# PiezoPreamp_VR.net
KiCad netlist of a schematic drawn in EAGLE
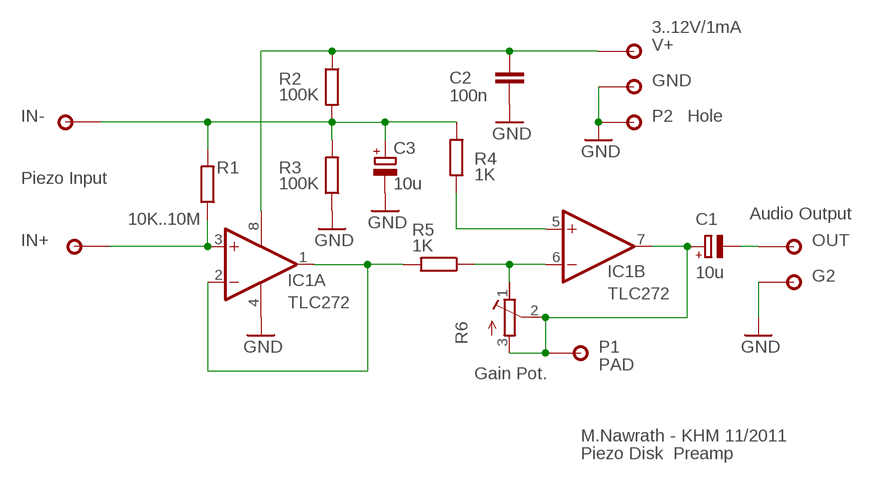
[diagram p0: schematic, sheet 1]

(export (version "E")
  (design (tool "Eeschema 10.0.6"))
  (components
    (comp (ref "C1")
      (value "10u")
      (footprint "eagle-import:E2,5-5")
      (libsource (lib "eagle-import") (part "CPOL-EUE2.5-5"))
    )
    (comp (ref "C2")
      (value "100n")
      (footprint "eagle-import:C025-025X050")
      (libsource (lib "eagle-import") (part "C-EU025-025X050"))
    )
    (comp (ref "C3")
      (value "10u")
      (footprint "eagle-import:E2,5-5")
      (libsource (lib "eagle-import") (part "CPOL-EUE2.5-5"))
    )
    (comp (ref "G2")
      (value "PAD1,46MM")
      (footprint "eagle-import:PAD146")
      (libsource (lib "eagle-import") (part "PAD1,46MM"))
    )
    (comp (ref "GND")
      (value "PAD1,46MM")
      (footprint "eagle-import:PAD146")
      (libsource (lib "eagle-import") (part "PAD1,46MM"))
    )
    (comp (ref "IC1")
      (value "TLC272")
      (footprint "eagle-import:DIL08")
      (libsource (lib "eagle-import") (part "TLC272P"))
    )
    (comp (ref "IN+")
      (value "PAD1,46MM")
      (footprint "eagle-import:PAD146")
      (libsource (lib "eagle-import") (part "PAD1,46MM"))
    )
    (comp (ref "IN-")
      (value "PAD1,46MM")
      (footprint "eagle-import:PAD146")
      (libsource (lib "eagle-import") (part "PAD1,46MM"))
    )
    (comp (ref "OUT")
      (value "PAD1,46MM")
      (footprint "eagle-import:PAD146")
      (libsource (lib "eagle-import") (part "PAD1,46MM"))
    )
    (comp (ref "P1")
      (value "PAD")
      (footprint "eagle-import:PAD127L1")
      (libsource (lib "eagle-import") (part "PADL2"))
    )
    (comp (ref "P2")
      (value "Hole")
      (footprint "eagle-import:PAD146")
      (libsource (lib "eagle-import") (part "PAD1,46MM"))
    )
    (comp (ref "R1")
      (value "10K..10M")
      (footprint "eagle-import:0207_10")
      (libsource (lib "eagle-import") (part "R-EU_0207/10"))
    )
    (comp (ref "R2")
      (value "100K")
      (footprint "eagle-import:0207_10")
      (libsource (lib "eagle-import") (part "R-EU_0207/10"))
    )
    (comp (ref "R3")
      (value "100K")
      (footprint "eagle-import:0207_10")
      (libsource (lib "eagle-import") (part "R-EU_0207/10"))
    )
    (comp (ref "R4")
      (value "1K")
      (footprint "eagle-import:0207_10")
      (libsource (lib "eagle-import") (part "R-EU_0207/10"))
    )
    (comp (ref "R5")
      (value "1K")
      (footprint "eagle-import:0207_10")
      (libsource (lib "eagle-import") (part "R-EU_0207/10"))
    )
    (comp (ref "R6")
      (value "R-TRIMM3006P")
      (footprint "eagle-import:RTRIM3006P")
      (libsource (lib "eagle-import") (part "R-TRIMM3006P"))
    )
    (comp (ref "V+")
      (value "PAD1,46MM")
      (footprint "eagle-import:PAD146")
      (libsource (lib "eagle-import") (part "PAD1,46MM"))
    )
  )
  (nets
    (net (code "1") (name "GND") (class "Default")
      (node (ref "C2") (pin "1") (pinfunction "1_1") (pintype "passive"))
      (node (ref "C3") (pin "-") (pinfunction "-_-") (pintype "passive"))
      (node (ref "G2") (pin "1") (pinfunction "1_1") (pintype "passive"))
      (node (ref "GND") (pin "1") (pinfunction "1_1") (pintype "passive"))
      (node (ref "IC1") (pin "4") (pinfunction "V-_4") (pintype "power_in"))
      (node (ref "P2") (pin "1") (pinfunction "1_1") (pintype "passive"))
      (node (ref "R3") (pin "1") (pinfunction "1_1") (pintype "passive"))
    )
    (net (code "2") (name "Net-(C1-Pad-)") (class "Default")
      (node (ref "C1") (pin "-") (pinfunction "-_-") (pintype "passive"))
      (node (ref "OUT") (pin "1") (pinfunction "1_1") (pintype "passive"))
    )
    (net (code "3") (name "Net-(C3-Pad+)") (class "Default")
      (node (ref "C3") (pin "+") (pinfunction "+_+") (pintype "passive"))
      (node (ref "IN-") (pin "1") (pinfunction "1_1") (pintype "passive"))
      (node (ref "R1") (pin "2") (pinfunction "2_2") (pintype "passive"))
      (node (ref "R2") (pin "2") (pinfunction "2_2") (pintype "passive"))
      (node (ref "R3") (pin "2") (pinfunction "2_2") (pintype "passive"))
      (node (ref "R4") (pin "2") (pinfunction "2_2") (pintype "passive"))
    )
    (net (code "4") (name "Net-(IC1A-+IN)") (class "Default")
      (node (ref "IC1") (pin "3") (pinfunction "+IN_3") (pintype "input"))
      (node (ref "IN+") (pin "1") (pinfunction "1_1") (pintype "passive"))
      (node (ref "R1") (pin "1") (pinfunction "1_1") (pintype "passive"))
    )
    (net (code "5") (name "Net-(IC1A--IN)") (class "Default")
      (node (ref "IC1") (pin "1") (pinfunction "OUT_1") (pintype "output"))
      (node (ref "IC1") (pin "2") (pinfunction "-IN_2") (pintype "input"))
      (node (ref "R5") (pin "2") (pinfunction "2_2") (pintype "passive"))
    )
    (net (code "6") (name "Net-(IC1B-+IN)") (class "Default")
      (node (ref "IC1") (pin "5") (pinfunction "+IN_5") (pintype "input"))
      (node (ref "R4") (pin "1") (pinfunction "1_1") (pintype "passive"))
    )
    (net (code "7") (name "Net-(IC1B--IN)") (class "Default")
      (node (ref "IC1") (pin "6") (pinfunction "-IN_6") (pintype "input"))
      (node (ref "R5") (pin "1") (pinfunction "1_1") (pintype "passive"))
      (node (ref "R6") (pin "1") (pinfunction "E_1") (pintype "passive"))
    )
    (net (code "8") (name "Net-(IC1B-OUT)") (class "Default")
      (node (ref "C1") (pin "+") (pinfunction "+_+") (pintype "passive"))
      (node (ref "IC1") (pin "7") (pinfunction "OUT_7") (pintype "output"))
      (node (ref "P1") (pin "P$2") (pinfunction "1_P$2") (pintype "passive"))
      (node (ref "R6") (pin "2") (pinfunction "S_2") (pintype "passive"))
      (node (ref "R6") (pin "3") (pinfunction "A_3") (pintype "passive"))
    )
    (net (code "9") (name "Net-(IC1C-V+)") (class "Default")
      (node (ref "C2") (pin "2") (pinfunction "2_2") (pintype "passive"))
      (node (ref "IC1") (pin "8") (pinfunction "V+_8") (pintype "power_in"))
      (node (ref "R2") (pin "1") (pinfunction "1_1") (pintype "passive"))
      (node (ref "V+") (pin "1") (pinfunction "1_1") (pintype "passive"))
    )
  )
)
